# untitled3.net
KiCad netlist of a schematic drawn in EAGLE
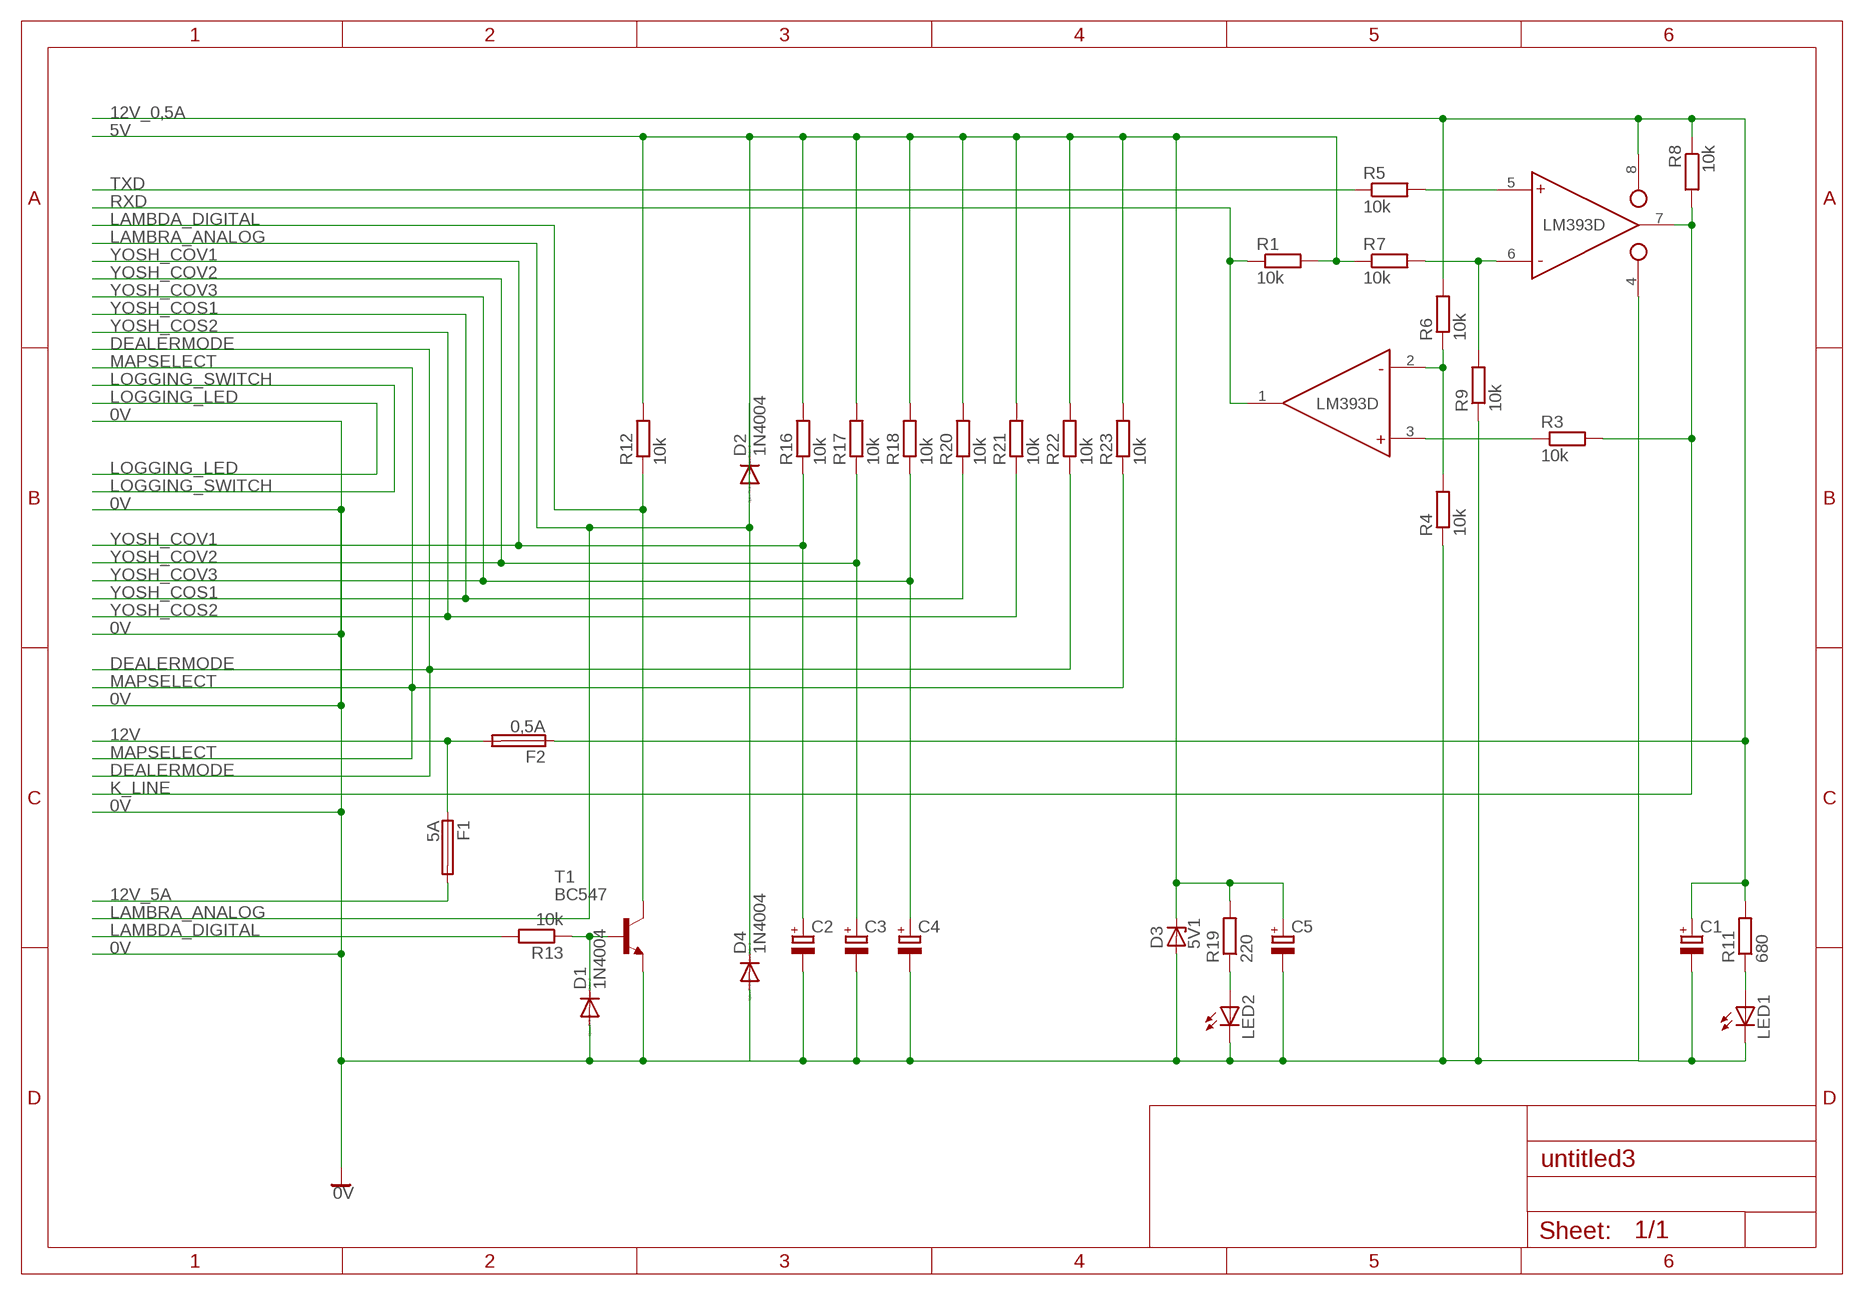
[diagram p0: schematic, sheet 1]

(export (version "E")
  (design (tool "Eeschema 10.0.6"))
  (components
    (comp (ref "C1")
      (value "CPOL-EUE1.8-4")
      (footprint "eagle-import:E1,8-4")
      (libsource (lib "eagle-import") (part "CPOL-EUE1.8-4"))
    )
    (comp (ref "C2")
      (value "CPOL-EUE1.8-4")
      (footprint "eagle-import:E1,8-4")
      (libsource (lib "eagle-import") (part "CPOL-EUE1.8-4"))
    )
    (comp (ref "C3")
      (value "CPOL-EUE1.8-4")
      (footprint "eagle-import:E1,8-4")
      (libsource (lib "eagle-import") (part "CPOL-EUE1.8-4"))
    )
    (comp (ref "C4")
      (value "CPOL-EUE1.8-4")
      (footprint "eagle-import:E1,8-4")
      (libsource (lib "eagle-import") (part "CPOL-EUE1.8-4"))
    )
    (comp (ref "C5")
      (value "CPOL-EUE1.8-4")
      (footprint "eagle-import:E1,8-4")
      (libsource (lib "eagle-import") (part "CPOL-EUE1.8-4"))
    )
    (comp (ref "D1")
      (value "1N4004")
      (footprint "eagle-import:DO41-10")
      (libsource (lib "eagle-import") (part "1N4004"))
    )
    (comp (ref "D2")
      (value "1N4004")
      (footprint "eagle-import:DO41-10")
      (libsource (lib "eagle-import") (part "1N4004"))
    )
    (comp (ref "D3")
      (value "5V1")
      (footprint "eagle-import:DO34Z7")
      (libsource (lib "eagle-import") (part "ZENER-DIODEDO34-7"))
    )
    (comp (ref "D4")
      (value "1N4004")
      (footprint "eagle-import:DO41-10")
      (libsource (lib "eagle-import") (part "1N4004"))
    )
    (comp (ref "F1")
      (value "5A")
      (footprint "eagle-import:SH22,5")
      (fields (field (name "MF") "SCHURTER") (field (name "MPN") "0031.8201"))
      (libsource (lib "eagle-import") (part "SH22,5"))
    )
    (comp (ref "F2")
      (value "0,5A")
      (footprint "eagle-import:SH22,5")
      (fields (field (name "MF") "SCHURTER") (field (name "MPN") "0031.8201"))
      (libsource (lib "eagle-import") (part "SH22,5"))
    )
    (comp (ref "LED1")
      (value "LED5MM")
      (footprint "eagle-import:LED5MM")
      (libsource (lib "eagle-import") (part "LED5MM"))
    )
    (comp (ref "LED2")
      (value "LED5MM")
      (footprint "eagle-import:LED5MM")
      (libsource (lib "eagle-import") (part "LED5MM"))
    )
    (comp (ref "R1")
      (value "10k")
      (footprint "eagle-import:0207_7")
      (libsource (lib "eagle-import") (part "R-EU_0207/7"))
    )
    (comp (ref "R3")
      (value "10k")
      (footprint "eagle-import:0207_7")
      (libsource (lib "eagle-import") (part "R-EU_0207/7"))
    )
    (comp (ref "R4")
      (value "10k")
      (footprint "eagle-import:0207_7")
      (libsource (lib "eagle-import") (part "R-EU_0207/7"))
    )
    (comp (ref "R5")
      (value "10k")
      (footprint "eagle-import:0207_7")
      (libsource (lib "eagle-import") (part "R-EU_0207/7"))
    )
    (comp (ref "R6")
      (value "10k")
      (footprint "eagle-import:0207_7")
      (libsource (lib "eagle-import") (part "R-EU_0207/7"))
    )
    (comp (ref "R7")
      (value "10k")
      (footprint "eagle-import:0207_7")
      (libsource (lib "eagle-import") (part "R-EU_0207/7"))
    )
    (comp (ref "R8")
      (value "10k")
      (footprint "eagle-import:0207_7")
      (libsource (lib "eagle-import") (part "R-EU_0207/7"))
    )
    (comp (ref "R9")
      (value "10k")
      (footprint "eagle-import:0207_7")
      (libsource (lib "eagle-import") (part "R-EU_0207/7"))
    )
    (comp (ref "R11")
      (value "680")
      (footprint "eagle-import:0207_7")
      (libsource (lib "eagle-import") (part "R-EU_0207/7"))
    )
    (comp (ref "R12")
      (value "10k")
      (footprint "eagle-import:0207_7")
      (libsource (lib "eagle-import") (part "R-EU_0207/7"))
    )
    (comp (ref "R13")
      (value "10k")
      (footprint "eagle-import:0207_7")
      (libsource (lib "eagle-import") (part "R-EU_0207/7"))
    )
    (comp (ref "R16")
      (value "10k")
      (footprint "eagle-import:0207_7")
      (libsource (lib "eagle-import") (part "R-EU_0207/7"))
    )
    (comp (ref "R17")
      (value "10k")
      (footprint "eagle-import:0207_7")
      (libsource (lib "eagle-import") (part "R-EU_0207/7"))
    )
    (comp (ref "R18")
      (value "10k")
      (footprint "eagle-import:0207_7")
      (libsource (lib "eagle-import") (part "R-EU_0207/7"))
    )
    (comp (ref "R19")
      (value "220")
      (footprint "eagle-import:0207_7")
      (libsource (lib "eagle-import") (part "R-EU_0207/7"))
    )
    (comp (ref "R20")
      (value "10k")
      (footprint "eagle-import:0207_7")
      (libsource (lib "eagle-import") (part "R-EU_0207/7"))
    )
    (comp (ref "R21")
      (value "10k")
      (footprint "eagle-import:0207_7")
      (libsource (lib "eagle-import") (part "R-EU_0207/7"))
    )
    (comp (ref "R22")
      (value "10k")
      (footprint "eagle-import:0207_7")
      (libsource (lib "eagle-import") (part "R-EU_0207/7"))
    )
    (comp (ref "R23")
      (value "10k")
      (footprint "eagle-import:0207_7")
      (libsource (lib "eagle-import") (part "R-EU_0207/7"))
    )
    (comp (ref "T1")
      (value "BC547")
      (footprint "eagle-import:TO92")
      (libsource (lib "eagle-import") (part "BC547"))
    )
    (comp (ref "U$1")
      (value "LM393D")
      (footprint "eagle-import:LM393D")
      (libsource (lib "eagle-import") (part "LM393D"))
    )
  )
  (nets
    (net (code "1") (name "/5V") (class "Default")
      (node (ref "C5") (pin "+") (pinfunction "+_+") (pintype "passive"))
      (node (ref "D2") (pin "C") (pinfunction "C_C") (pintype "passive"))
      (node (ref "D3") (pin "C") (pinfunction "C_C") (pintype "passive"))
      (node (ref "R1") (pin "2") (pinfunction "2_2") (pintype "passive"))
      (node (ref "R12") (pin "2") (pinfunction "2_2") (pintype "passive"))
      (node (ref "R16") (pin "2") (pinfunction "2_2") (pintype "passive"))
      (node (ref "R17") (pin "2") (pinfunction "2_2") (pintype "passive"))
      (node (ref "R18") (pin "2") (pinfunction "2_2") (pintype "passive"))
      (node (ref "R19") (pin "2") (pinfunction "2_2") (pintype "passive"))
      (node (ref "R20") (pin "2") (pinfunction "2_2") (pintype "passive"))
      (node (ref "R21") (pin "2") (pinfunction "2_2") (pintype "passive"))
      (node (ref "R22") (pin "2") (pinfunction "2_2") (pintype "passive"))
      (node (ref "R23") (pin "2") (pinfunction "2_2") (pintype "passive"))
      (node (ref "R7") (pin "1") (pinfunction "1_1") (pintype "passive"))
    )
    (net (code "2") (name "/12V") (class "Default")
      (node (ref "F1") (pin "1") (pinfunction "1_1") (pintype "passive"))
      (node (ref "F2") (pin "2") (pinfunction "2_2") (pintype "passive"))
    )
    (net (code "3") (name "/12V_0,5A") (class "Default")
      (node (ref "C1") (pin "+") (pinfunction "+_+") (pintype "passive"))
      (node (ref "F2") (pin "1") (pinfunction "1_1") (pintype "passive"))
      (node (ref "R11") (pin "2") (pinfunction "2_2") (pintype "passive"))
      (node (ref "R6") (pin "2") (pinfunction "2_2") (pintype "passive"))
      (node (ref "R8") (pin "1") (pinfunction "1_1") (pintype "passive"))
      (node (ref "U$1") (pin "8") (pinfunction "VCC_8") (pintype "power_in"))
    )
    (net (code "4") (name "/12V_5A") (class "Default")
      (node (ref "F1") (pin "2") (pinfunction "2_2") (pintype "passive"))
    )
    (net (code "5") (name "/DEALERMODE") (class "Default")
      (node (ref "R22") (pin "1") (pinfunction "1_1") (pintype "passive"))
    )
    (net (code "6") (name "/K_LINE") (class "Default")
      (node (ref "R3") (pin "2") (pinfunction "2_2") (pintype "passive"))
      (node (ref "R8") (pin "2") (pinfunction "2_2") (pintype "passive"))
      (node (ref "U$1") (pin "7") (pinfunction "OUT_7") (pintype "output"))
    )
    (net (code "7") (name "/LAMBDA_DIGITAL") (class "Default")
      (node (ref "R12") (pin "1") (pinfunction "1_1") (pintype "passive"))
      (node (ref "R13") (pin "2") (pinfunction "2_2") (pintype "passive"))
      (node (ref "T1") (pin "3") (pinfunction "C_3") (pintype "passive"))
    )
    (net (code "8") (name "/LAMBRA_ANALOG") (class "Default")
      (node (ref "D2") (pin "A") (pinfunction "A_A") (pintype "passive"))
      (node (ref "D4") (pin "C") (pinfunction "C_C") (pintype "passive"))
    )
    (net (code "11") (name "/MAPSELECT") (class "Default")
      (node (ref "R23") (pin "1") (pinfunction "1_1") (pintype "passive"))
    )
    (net (code "12") (name "/RXD") (class "Default")
      (node (ref "R1") (pin "1") (pinfunction "1_1") (pintype "passive"))
      (node (ref "U$1") (pin "1") (pinfunction "OUT_1") (pintype "output"))
    )
    (net (code "13") (name "/TXD") (class "Default")
      (node (ref "R5") (pin "1") (pinfunction "1_1") (pintype "passive"))
    )
    (net (code "14") (name "/YOSH_COS1") (class "Default")
      (node (ref "R20") (pin "1") (pinfunction "1_1") (pintype "passive"))
    )
    (net (code "15") (name "/YOSH_COS2") (class "Default")
      (node (ref "R21") (pin "1") (pinfunction "1_1") (pintype "passive"))
    )
    (net (code "16") (name "/YOSH_COV1") (class "Default")
      (node (ref "C2") (pin "+") (pinfunction "+_+") (pintype "passive"))
      (node (ref "R16") (pin "1") (pinfunction "1_1") (pintype "passive"))
    )
    (net (code "17") (name "/YOSH_COV2") (class "Default")
      (node (ref "C3") (pin "+") (pinfunction "+_+") (pintype "passive"))
      (node (ref "R17") (pin "1") (pinfunction "1_1") (pintype "passive"))
    )
    (net (code "18") (name "/YOSH_COV3") (class "Default")
      (node (ref "C4") (pin "+") (pinfunction "+_+") (pintype "passive"))
      (node (ref "R18") (pin "1") (pinfunction "1_1") (pintype "passive"))
    )
    (net (code "19") (name "0V") (class "Default")
      (node (ref "C1") (pin "-") (pinfunction "-_-") (pintype "passive"))
      (node (ref "C2") (pin "-") (pinfunction "-_-") (pintype "passive"))
      (node (ref "C3") (pin "-") (pinfunction "-_-") (pintype "passive"))
      (node (ref "C4") (pin "-") (pinfunction "-_-") (pintype "passive"))
      (node (ref "C5") (pin "-") (pinfunction "-_-") (pintype "passive"))
      (node (ref "D1") (pin "A") (pinfunction "A_A") (pintype "passive"))
      (node (ref "D3") (pin "A") (pinfunction "A_A") (pintype "passive"))
      (node (ref "D4") (pin "A") (pinfunction "A_A") (pintype "passive"))
      (node (ref "LED1") (pin "K") (pinfunction "C_K") (pintype "passive"))
      (node (ref "LED2") (pin "K") (pinfunction "C_K") (pintype "passive"))
      (node (ref "R4") (pin "1") (pinfunction "1_1") (pintype "passive"))
      (node (ref "R9") (pin "1") (pinfunction "1_1") (pintype "passive"))
      (node (ref "T1") (pin "1") (pinfunction "E_1") (pintype "passive"))
      (node (ref "U$1") (pin "4") (pinfunction "GND_4") (pintype "power_in"))
    )
    (net (code "20") (name "Net-(LED1-PadA)") (class "Default")
      (node (ref "LED1") (pin "A") (pinfunction "A_A") (pintype "passive"))
      (node (ref "R11") (pin "1") (pinfunction "1_1") (pintype "passive"))
    )
    (net (code "21") (name "Net-(LED2-PadA)") (class "Default")
      (node (ref "LED2") (pin "A") (pinfunction "A_A") (pintype "passive"))
      (node (ref "R19") (pin "1") (pinfunction "1_1") (pintype "passive"))
    )
    (net (code "22") (name "Net-(T1-B)") (class "Default")
      (node (ref "D1") (pin "C") (pinfunction "C_C") (pintype "passive"))
      (node (ref "R13") (pin "1") (pinfunction "1_1") (pintype "passive"))
      (node (ref "T1") (pin "2") (pinfunction "B_2") (pintype "passive"))
    )
    (net (code "23") (name "Net-(U$1B-IN+)") (class "Default")
      (node (ref "R3") (pin "1") (pinfunction "1_1") (pintype "passive"))
      (node (ref "U$1") (pin "3") (pinfunction "IN+_3") (pintype "input"))
    )
    (net (code "24") (name "Net-(U$1B-IN-)") (class "Default")
      (node (ref "R4") (pin "2") (pinfunction "2_2") (pintype "passive"))
      (node (ref "R6") (pin "1") (pinfunction "1_1") (pintype "passive"))
      (node (ref "U$1") (pin "2") (pinfunction "IN-_2") (pintype "input"))
    )
    (net (code "25") (name "Net-(U$1C-IN+)") (class "Default")
      (node (ref "R5") (pin "2") (pinfunction "2_2") (pintype "passive"))
      (node (ref "U$1") (pin "5") (pinfunction "IN+_5") (pintype "input"))
    )
    (net (code "26") (name "Net-(U$1C-IN-)") (class "Default")
      (node (ref "R7") (pin "2") (pinfunction "2_2") (pintype "passive"))
      (node (ref "R9") (pin "2") (pinfunction "2_2") (pintype "passive"))
      (node (ref "U$1") (pin "6") (pinfunction "IN-_6") (pintype "input"))
    )
  )
)
